# LCD_TFT-Xplained_V1.net
KiCad netlist of a schematic drawn in EAGLE
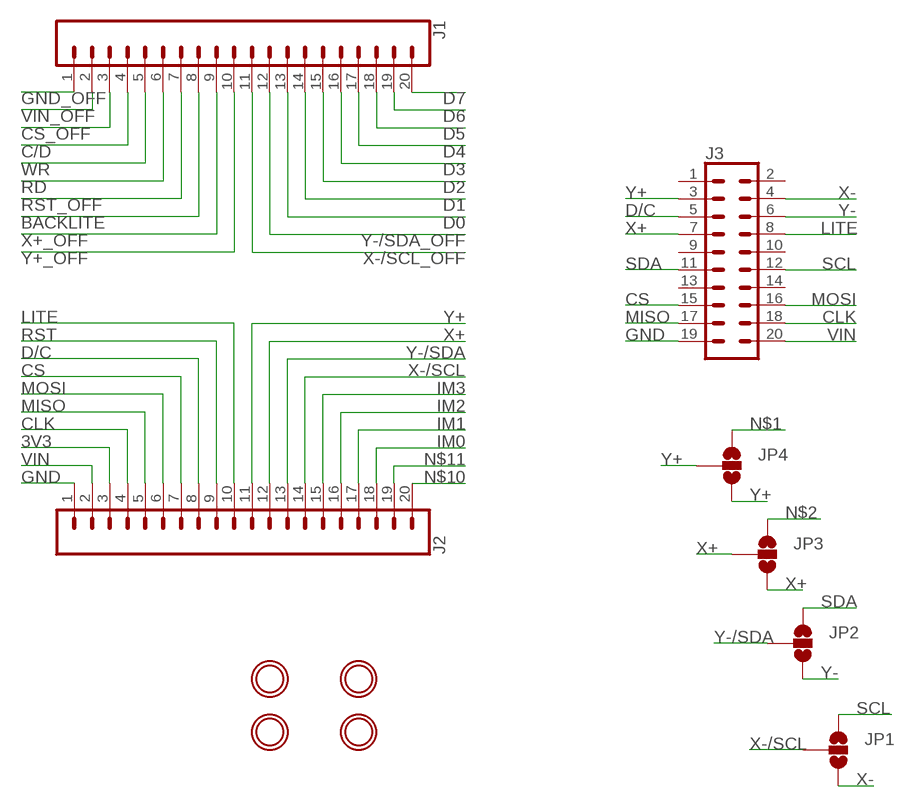
[diagram p0: schematic, sheet 1]

(export (version "E")
  (design (tool "Eeschema 10.0.6"))
  (components
    (comp (ref "J1")
      (value "CONN_20NOSILK")
      (footprint "eagle-import:1X20_NOSILK")
      (libsource (lib "eagle-import") (part "CONN_20NOSILK"))
    )
    (comp (ref "J2")
      (value "CONN_20NOSILK")
      (footprint "eagle-import:1X20_NOSILK")
      (libsource (lib "eagle-import") (part "CONN_20NOSILK"))
    )
    (comp (ref "J3")
      (value "CONN_10X2")
      (footprint "eagle-import:2X10")
      (libsource (lib "eagle-import") (part "CONN_10X2"))
    )
    (comp (ref "JP1")
      (value "JUMPER-SMT_3_NO_NO-SILK")
      (footprint "eagle-import:SMT-JUMPER_3_NO_NO-SILK")
      (libsource (lib "eagle-import") (part "JUMPER-SMT_3_NO_NO-SILK"))
    )
    (comp (ref "JP2")
      (value "JUMPER-SMT_3_NO_NO-SILK")
      (footprint "eagle-import:SMT-JUMPER_3_NO_NO-SILK")
      (libsource (lib "eagle-import") (part "JUMPER-SMT_3_NO_NO-SILK"))
    )
    (comp (ref "JP3")
      (value "JUMPER-SMT_3_NO_NO-SILK")
      (footprint "eagle-import:SMT-JUMPER_3_NO_NO-SILK")
      (libsource (lib "eagle-import") (part "JUMPER-SMT_3_NO_NO-SILK"))
    )
    (comp (ref "JP4")
      (value "JUMPER-SMT_3_NO_NO-SILK")
      (footprint "eagle-import:SMT-JUMPER_3_NO_NO-SILK")
      (libsource (lib "eagle-import") (part "JUMPER-SMT_3_NO_NO-SILK"))
    )
    (comp (ref "U$1")
      (value "MOUNTINGHOLE3.0THIN")
      (footprint "eagle-import:MOUNTINGHOLE_3.0_PLATEDTHIN")
      (libsource (lib "eagle-import") (part "MOUNTINGHOLE3.0THIN"))
    )
    (comp (ref "U$2")
      (value "MOUNTINGHOLE3.0THIN")
      (footprint "eagle-import:MOUNTINGHOLE_3.0_PLATEDTHIN")
      (libsource (lib "eagle-import") (part "MOUNTINGHOLE3.0THIN"))
    )
    (comp (ref "U$3")
      (value "MOUNTINGHOLE3.0THIN")
      (footprint "eagle-import:MOUNTINGHOLE_3.0_PLATEDTHIN")
      (libsource (lib "eagle-import") (part "MOUNTINGHOLE3.0THIN"))
    )
    (comp (ref "U$4")
      (value "MOUNTINGHOLE3.0THIN")
      (footprint "eagle-import:MOUNTINGHOLE_3.0_PLATEDTHIN")
      (libsource (lib "eagle-import") (part "MOUNTINGHOLE3.0THIN"))
    )
  )
  (nets
    (net (code "1") (name "/3V3") (class "Default")
      (node (ref "J2") (pin "3") (pinfunction "3_3") (pintype "passive"))
    )
    (net (code "2") (name "/BACKLITE") (class "Default")
      (node (ref "J1") (pin "8") (pinfunction "8_8") (pintype "passive"))
    )
    (net (code "3") (name "/CLK") (class "Default")
      (node (ref "J2") (pin "4") (pinfunction "4_4") (pintype "passive"))
      (node (ref "J3") (pin "18") (pinfunction "18_18") (pintype "passive"))
    )
    (net (code "4") (name "/CS") (class "Default")
      (node (ref "J2") (pin "7") (pinfunction "7_7") (pintype "passive"))
      (node (ref "J3") (pin "15") (pinfunction "15_15") (pintype "passive"))
    )
    (net (code "5") (name "/CS_OFF") (class "Default")
      (node (ref "J1") (pin "3") (pinfunction "3_3") (pintype "passive"))
    )
    (net (code "6") (name "/C{slash}D") (class "Default")
      (node (ref "J1") (pin "4") (pinfunction "4_4") (pintype "passive"))
    )
    (net (code "7") (name "/D0") (class "Default")
      (node (ref "J1") (pin "13") (pinfunction "13_13") (pintype "passive"))
    )
    (net (code "8") (name "/D1") (class "Default")
      (node (ref "J1") (pin "14") (pinfunction "14_14") (pintype "passive"))
    )
    (net (code "9") (name "/D2") (class "Default")
      (node (ref "J1") (pin "15") (pinfunction "15_15") (pintype "passive"))
    )
    (net (code "10") (name "/D3") (class "Default")
      (node (ref "J1") (pin "16") (pinfunction "16_16") (pintype "passive"))
    )
    (net (code "11") (name "/D4") (class "Default")
      (node (ref "J1") (pin "17") (pinfunction "17_17") (pintype "passive"))
    )
    (net (code "12") (name "/D5") (class "Default")
      (node (ref "J1") (pin "18") (pinfunction "18_18") (pintype "passive"))
    )
    (net (code "13") (name "/D6") (class "Default")
      (node (ref "J1") (pin "19") (pinfunction "19_19") (pintype "passive"))
    )
    (net (code "14") (name "/D7") (class "Default")
      (node (ref "J1") (pin "20") (pinfunction "20_20") (pintype "passive"))
    )
    (net (code "15") (name "/D{slash}C") (class "Default")
      (node (ref "J2") (pin "8") (pinfunction "8_8") (pintype "passive"))
      (node (ref "J3") (pin "5") (pinfunction "5_5") (pintype "passive"))
    )
    (net (code "16") (name "/GND") (class "Default")
      (node (ref "J2") (pin "1") (pinfunction "1_1") (pintype "passive"))
      (node (ref "J3") (pin "19") (pinfunction "19_19") (pintype "passive"))
    )
    (net (code "17") (name "/GND_OFF") (class "Default")
      (node (ref "J1") (pin "1") (pinfunction "1_1") (pintype "passive"))
    )
    (net (code "18") (name "/IM0") (class "Default")
      (node (ref "J2") (pin "18") (pinfunction "18_18") (pintype "passive"))
    )
    (net (code "19") (name "/IM1") (class "Default")
      (node (ref "J2") (pin "17") (pinfunction "17_17") (pintype "passive"))
    )
    (net (code "20") (name "/IM2") (class "Default")
      (node (ref "J2") (pin "16") (pinfunction "16_16") (pintype "passive"))
    )
    (net (code "21") (name "/IM3") (class "Default")
      (node (ref "J2") (pin "15") (pinfunction "15_15") (pintype "passive"))
    )
    (net (code "22") (name "/LITE") (class "Default")
      (node (ref "J2") (pin "10") (pinfunction "10_10") (pintype "passive"))
      (node (ref "J3") (pin "8") (pinfunction "8_8") (pintype "passive"))
    )
    (net (code "23") (name "/MISO") (class "Default")
      (node (ref "J2") (pin "5") (pinfunction "5_5") (pintype "passive"))
      (node (ref "J3") (pin "17") (pinfunction "17_17") (pintype "passive"))
    )
    (net (code "24") (name "/MOSI") (class "Default")
      (node (ref "J2") (pin "6") (pinfunction "6_6") (pintype "passive"))
      (node (ref "J3") (pin "16") (pinfunction "16_16") (pintype "passive"))
    )
    (net (code "25") (name "/N$1") (class "Default")
      (node (ref "JP4") (pin "1") (pinfunction "1_1") (pintype "passive"))
    )
    (net (code "26") (name "/N$2") (class "Default")
      (node (ref "JP3") (pin "1") (pinfunction "1_1") (pintype "passive"))
    )
    (net (code "27") (name "/N$10") (class "Default")
      (node (ref "J2") (pin "20") (pinfunction "20_20") (pintype "passive"))
    )
    (net (code "28") (name "/N$11") (class "Default")
      (node (ref "J2") (pin "19") (pinfunction "19_19") (pintype "passive"))
    )
    (net (code "29") (name "/RD") (class "Default")
      (node (ref "J1") (pin "6") (pinfunction "6_6") (pintype "passive"))
    )
    (net (code "30") (name "/RST") (class "Default")
      (node (ref "J2") (pin "9") (pinfunction "9_9") (pintype "passive"))
    )
    (net (code "31") (name "/RST_OFF") (class "Default")
      (node (ref "J1") (pin "7") (pinfunction "7_7") (pintype "passive"))
    )
    (net (code "32") (name "/SCL") (class "Default")
      (node (ref "J3") (pin "12") (pinfunction "12_12") (pintype "passive"))
      (node (ref "JP1") (pin "1") (pinfunction "1_1") (pintype "passive"))
    )
    (net (code "33") (name "/SDA") (class "Default")
      (node (ref "J3") (pin "11") (pinfunction "11_11") (pintype "passive"))
      (node (ref "JP2") (pin "1") (pinfunction "1_1") (pintype "passive"))
    )
    (net (code "34") (name "/VIN") (class "Default")
      (node (ref "J2") (pin "2") (pinfunction "2_2") (pintype "passive"))
      (node (ref "J3") (pin "20") (pinfunction "20_20") (pintype "passive"))
    )
    (net (code "35") (name "/VIN_OFF") (class "Default")
      (node (ref "J1") (pin "2") (pinfunction "2_2") (pintype "passive"))
    )
    (net (code "36") (name "/WR") (class "Default")
      (node (ref "J1") (pin "5") (pinfunction "5_5") (pintype "passive"))
    )
    (net (code "37") (name "/X+") (class "Default")
      (node (ref "J2") (pin "12") (pinfunction "12_12") (pintype "passive"))
      (node (ref "J3") (pin "7") (pinfunction "7_7") (pintype "passive"))
      (node (ref "JP3") (pin "2") (pinfunction "2_2") (pintype "passive"))
      (node (ref "JP3") (pin "3") (pinfunction "3_3") (pintype "passive"))
    )
    (net (code "38") (name "/X+_OFF") (class "Default")
      (node (ref "J1") (pin "9") (pinfunction "9_9") (pintype "passive"))
    )
    (net (code "39") (name "/X-") (class "Default")
      (node (ref "J3") (pin "4") (pinfunction "4_4") (pintype "passive"))
      (node (ref "JP1") (pin "3") (pinfunction "3_3") (pintype "passive"))
    )
    (net (code "40") (name "/X-{slash}SCL") (class "Default")
      (node (ref "J2") (pin "14") (pinfunction "14_14") (pintype "passive"))
      (node (ref "JP1") (pin "2") (pinfunction "2_2") (pintype "passive"))
    )
    (net (code "41") (name "/X-{slash}SCL_OFF") (class "Default")
      (node (ref "J1") (pin "11") (pinfunction "11_11") (pintype "passive"))
    )
    (net (code "42") (name "/Y+") (class "Default")
      (node (ref "J2") (pin "11") (pinfunction "11_11") (pintype "passive"))
      (node (ref "J3") (pin "3") (pinfunction "3_3") (pintype "passive"))
      (node (ref "JP4") (pin "2") (pinfunction "2_2") (pintype "passive"))
      (node (ref "JP4") (pin "3") (pinfunction "3_3") (pintype "passive"))
    )
    (net (code "43") (name "/Y+_OFF") (class "Default")
      (node (ref "J1") (pin "10") (pinfunction "10_10") (pintype "passive"))
    )
    (net (code "44") (name "/Y-") (class "Default")
      (node (ref "J3") (pin "6") (pinfunction "6_6") (pintype "passive"))
      (node (ref "JP2") (pin "3") (pinfunction "3_3") (pintype "passive"))
    )
    (net (code "45") (name "/Y-{slash}SDA") (class "Default")
      (node (ref "J2") (pin "13") (pinfunction "13_13") (pintype "passive"))
      (node (ref "JP2") (pin "2") (pinfunction "2_2") (pintype "passive"))
    )
    (net (code "46") (name "/Y-{slash}SDA_OFF") (class "Default")
      (node (ref "J1") (pin "12") (pinfunction "12_12") (pintype "passive"))
    )
    (net (code "47") (name "unconnected-(J3-Pad1)") (class "Default")
      (node (ref "J3") (pin "1") (pinfunction "1_1") (pintype "passive"))
    )
    (net (code "48") (name "unconnected-(J3-Pad2)") (class "Default")
      (node (ref "J3") (pin "2") (pinfunction "2_2") (pintype "passive"))
    )
    (net (code "49") (name "unconnected-(J3-Pad9)") (class "Default")
      (node (ref "J3") (pin "9") (pinfunction "9_9") (pintype "passive"))
    )
    (net (code "50") (name "unconnected-(J3-Pad10)") (class "Default")
      (node (ref "J3") (pin "10") (pinfunction "10_10") (pintype "passive"))
    )
    (net (code "51") (name "unconnected-(J3-Pad13)") (class "Default")
      (node (ref "J3") (pin "13") (pinfunction "13_13") (pintype "passive"))
    )
    (net (code "52") (name "unconnected-(J3-Pad14)") (class "Default")
      (node (ref "J3") (pin "14") (pinfunction "14_14") (pintype "passive"))
    )
  )
)
